# 4-channel-1001-to-1-attenuator.net
KiCad netlist of a schematic drawn in EasyEDA
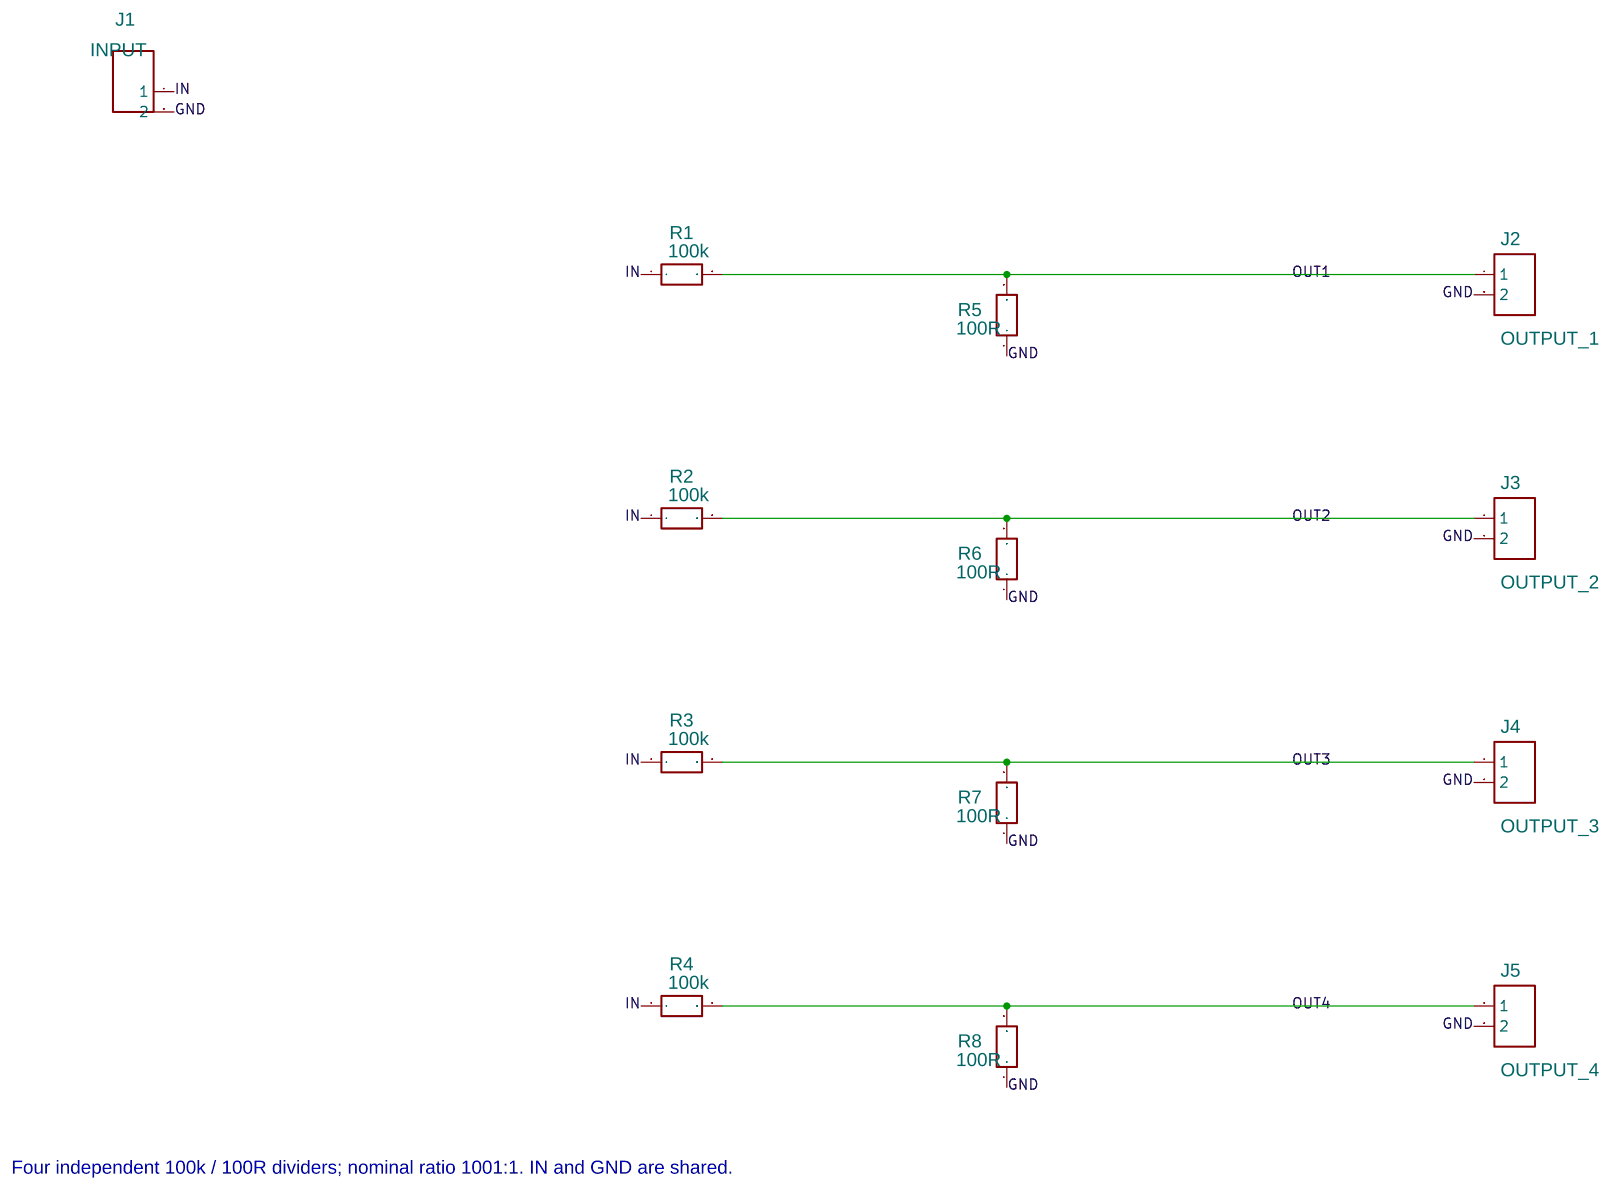
[diagram p0: schematic sheet]

(export (version "E")
  (design (tool "Eeschema 10.0.6"))
  (components
    (comp (ref "J1") (value "INPUT") (libsource (lib "") (part "HDR-M-2.54_1x2_1")))
    (comp (ref "J2") (value "OUTPUT_1") (libsource (lib "") (part "HDR-M-2.54_1x2")))
    (comp (ref "J3") (value "OUTPUT_2") (libsource (lib "") (part "HDR-M-2.54_1x2")))
    (comp (ref "J4") (value "OUTPUT_3") (libsource (lib "") (part "HDR-M-2.54_1x2")))
    (comp (ref "J5") (value "OUTPUT_4") (libsource (lib "") (part "HDR-M-2.54_1x2")))
    (comp (ref "R1") (value "100k") (libsource (lib "") (part "R_0805_EU")))
    (comp (ref "R2") (value "100k") (libsource (lib "") (part "R_0805_EU")))
    (comp (ref "R3") (value "100k") (libsource (lib "") (part "R_0805_EU")))
    (comp (ref "R4") (value "100k") (libsource (lib "") (part "R_0805_EU")))
    (comp (ref "R5") (value "100R") (libsource (lib "") (part "R_0805_EU_1")))
    (comp (ref "R6") (value "100R") (libsource (lib "") (part "R_0805_EU_1")))
    (comp (ref "R7") (value "100R") (libsource (lib "") (part "R_0805_EU_1")))
    (comp (ref "R8") (value "100R") (libsource (lib "") (part "R_0805_EU_1")))
  )
  (nets
    (net (code "1") (name "/GND") (class "Default")
      (node (ref "J1") (pin "2") (pinfunction "2_2") (pintype "unspecified"))
      (node (ref "J2") (pin "2") (pinfunction "2_2") (pintype "unspecified"))
      (node (ref "J3") (pin "2") (pinfunction "2_2") (pintype "unspecified"))
      (node (ref "J4") (pin "2") (pinfunction "2_2") (pintype "unspecified"))
      (node (ref "J5") (pin "2") (pinfunction "2_2") (pintype "unspecified"))
      (node (ref "R5") (pin "1") (pinfunction "1_1") (pintype "unspecified"))
      (node (ref "R6") (pin "1") (pinfunction "1_1") (pintype "unspecified"))
      (node (ref "R7") (pin "1") (pinfunction "1_1") (pintype "unspecified"))
      (node (ref "R8") (pin "1") (pinfunction "1_1") (pintype "unspecified"))
    )
    (net (code "2") (name "/IN") (class "Default")
      (node (ref "J1") (pin "1") (pinfunction "1_1") (pintype "unspecified"))
      (node (ref "R1") (pin "1") (pinfunction "1_1") (pintype "unspecified"))
      (node (ref "R2") (pin "1") (pinfunction "1_1") (pintype "unspecified"))
      (node (ref "R3") (pin "1") (pinfunction "1_1") (pintype "unspecified"))
      (node (ref "R4") (pin "1") (pinfunction "1_1") (pintype "unspecified"))
    )
    (net (code "3") (name "/OUT1") (class "Default")
      (node (ref "J2") (pin "1") (pinfunction "1_1") (pintype "unspecified"))
      (node (ref "R1") (pin "2") (pinfunction "2_2") (pintype "unspecified"))
      (node (ref "R5") (pin "2") (pinfunction "2_2") (pintype "unspecified"))
    )
    (net (code "4") (name "/OUT2") (class "Default")
      (node (ref "J3") (pin "1") (pinfunction "1_1") (pintype "unspecified"))
      (node (ref "R2") (pin "2") (pinfunction "2_2") (pintype "unspecified"))
      (node (ref "R6") (pin "2") (pinfunction "2_2") (pintype "unspecified"))
    )
    (net (code "5") (name "/OUT3") (class "Default")
      (node (ref "J4") (pin "1") (pinfunction "1_1") (pintype "unspecified"))
      (node (ref "R3") (pin "2") (pinfunction "2_2") (pintype "unspecified"))
      (node (ref "R7") (pin "2") (pinfunction "2_2") (pintype "unspecified"))
    )
    (net (code "6") (name "/OUT4") (class "Default")
      (node (ref "J5") (pin "1") (pinfunction "1_1") (pintype "unspecified"))
      (node (ref "R4") (pin "2") (pinfunction "2_2") (pintype "unspecified"))
      (node (ref "R8") (pin "2") (pinfunction "2_2") (pintype "unspecified"))
    )
  )
)
